# led.net
KiCad netlist of a schematic drawn in Altium Designer
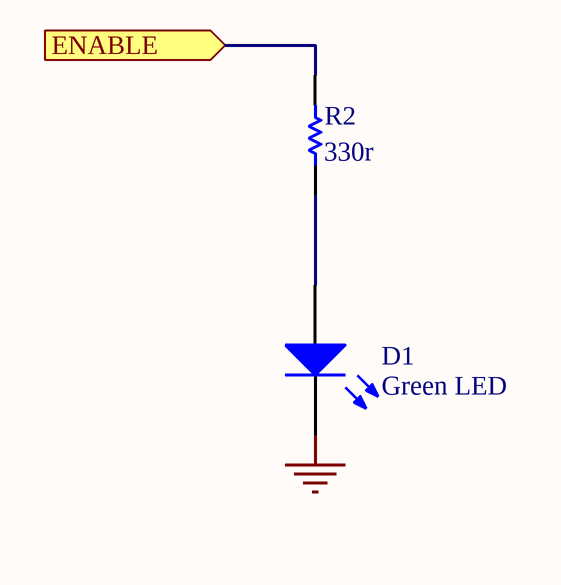
[diagram p0: led.SchDoc]

(export (version "E")
  (design (tool "Eeschema 10.0.6"))
  (components
    (comp (ref "D1")
      (value "Green LED")
      (footprint "LED_0805")
      (description "Typical INFRARED GaAs LED")
      (fields (field (name "PUBLISHER") "Altium Limited"))
      (libsource (lib "Miscellaneous Devices") (part "LED0"))
    )
    (comp (ref "R2")
      (value "330r")
      (footprint "RESC1608N")
      (description "Resistor")
      (fields (field (name "Comment") "Comment") (field (name "PUBLISHER") "Altium Limited"))
      (libsource (lib "Miscellaneous Devices") (part "Res1"))
    )
  )
  (nets
    (net (code "1") (name "/ENABLE") (class "Default")
      (node (ref "R2") (pin "2") (pinfunction "2_2") (pintype "passive"))
    )
    (net (code "2") (name "GND") (class "Default")
      (node (ref "D1") (pin "2") (pinfunction "K_2") (pintype "passive"))
    )
    (net (code "3") (name "Net-(D1-A)") (class "Default")
      (node (ref "D1") (pin "1") (pinfunction "A_1") (pintype "passive"))
      (node (ref "R2") (pin "1") (pinfunction "1_1") (pintype "passive"))
    )
  )
)
